# main.net
KiCad netlist of a schematic drawn in Altium Designer
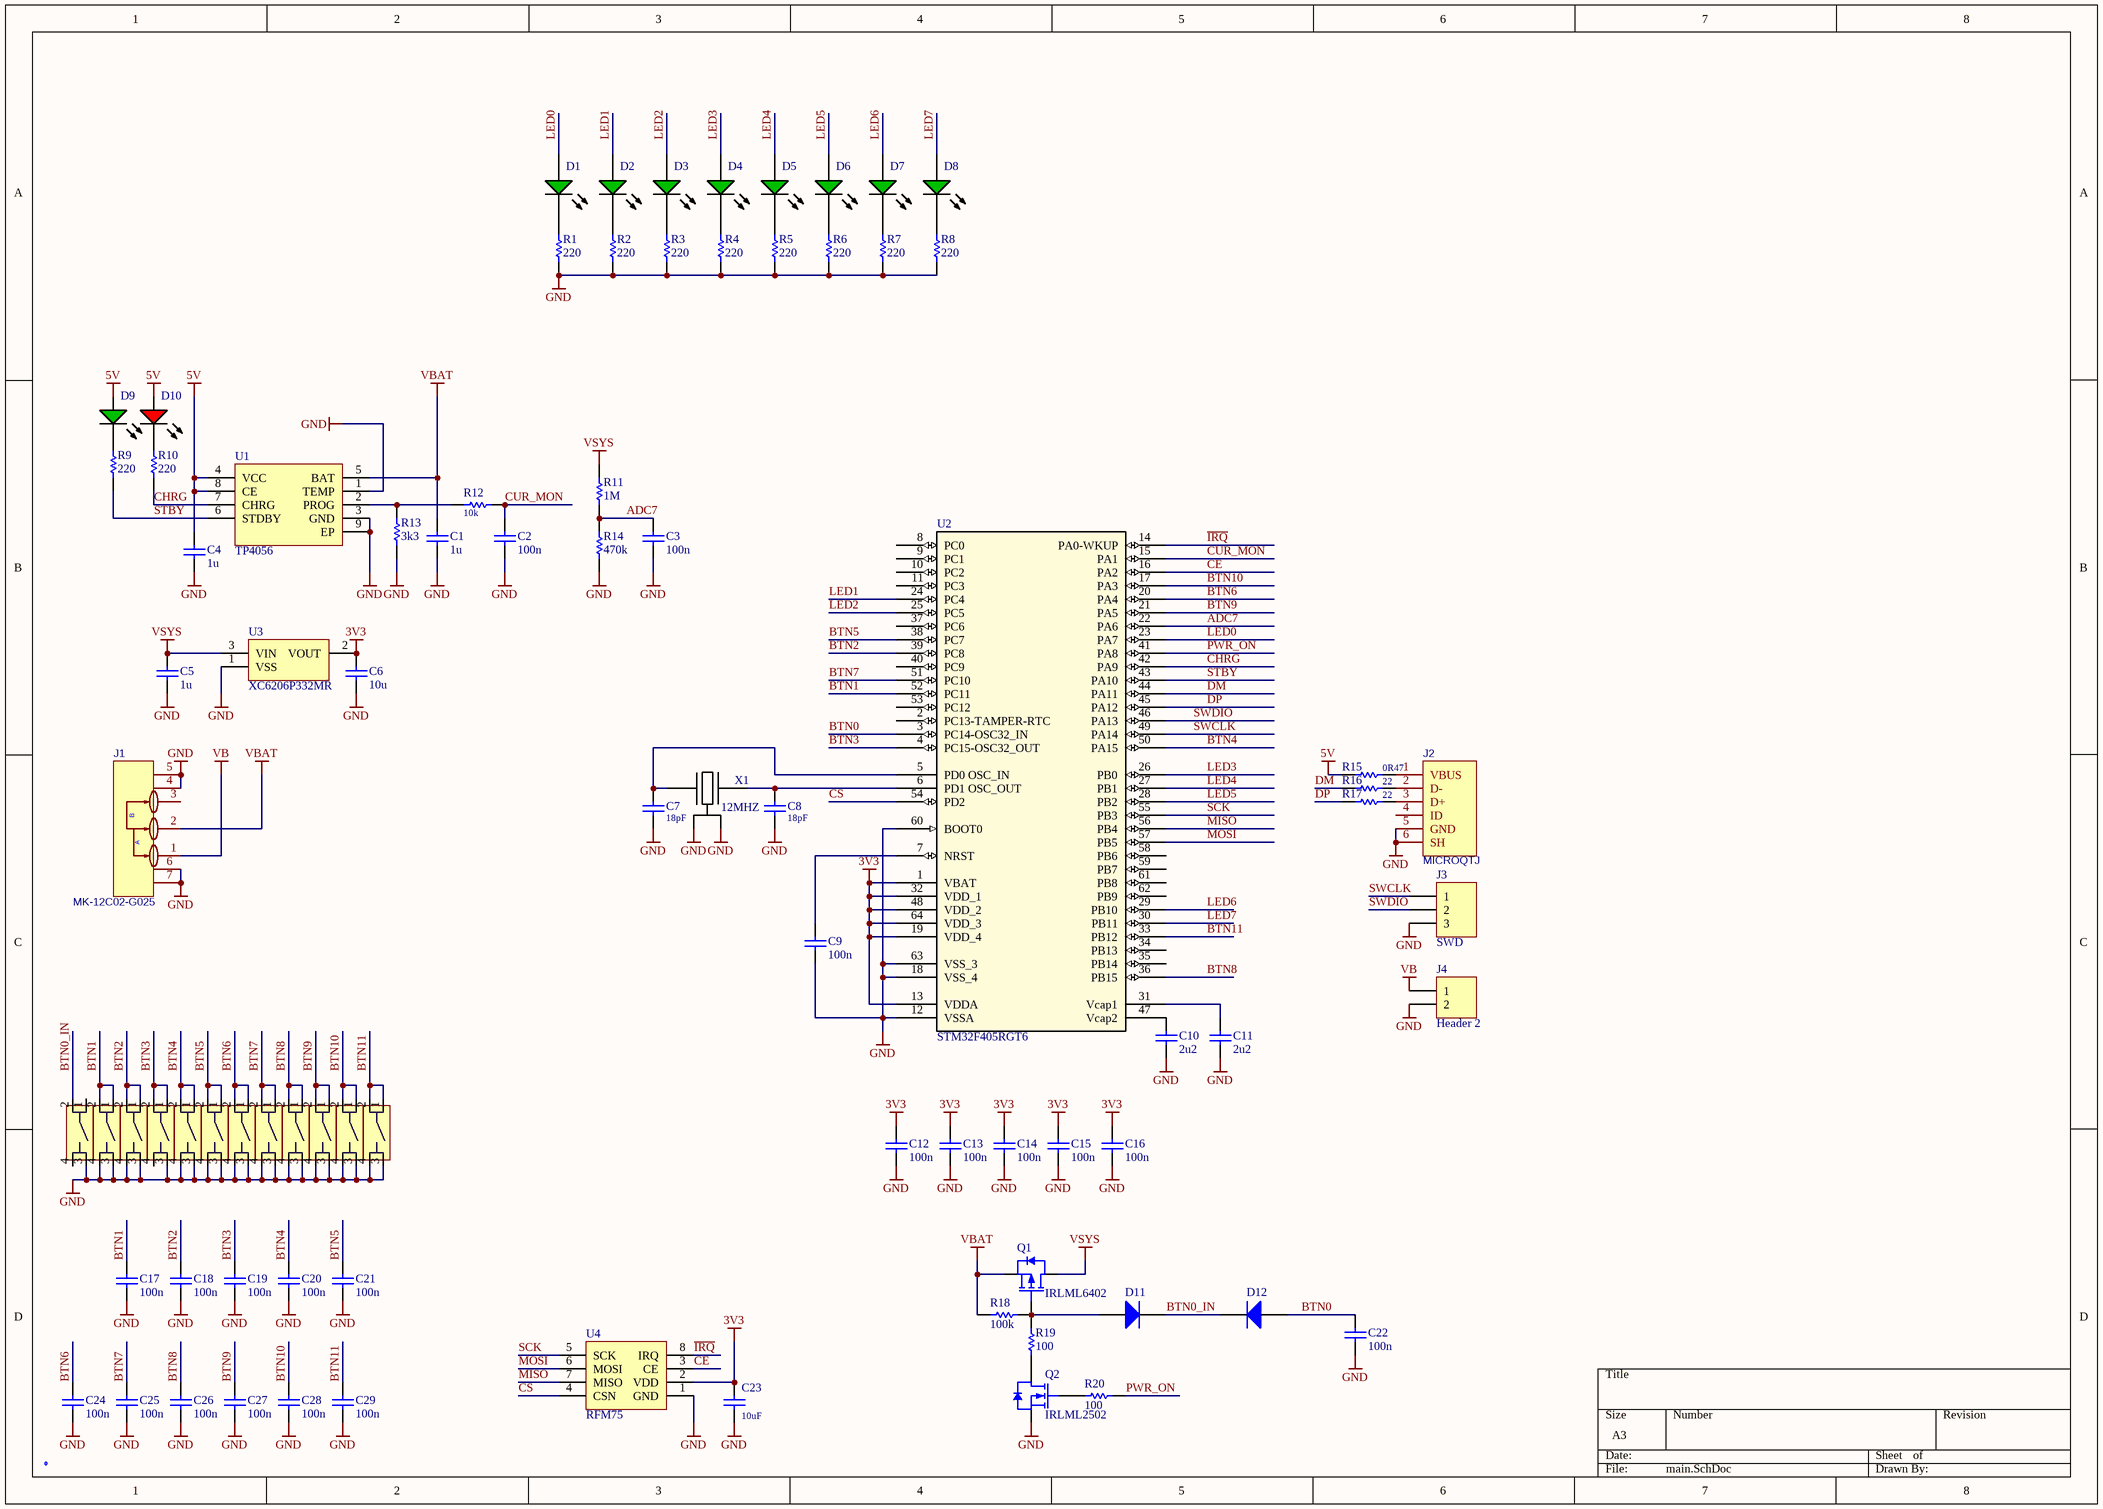
[diagram p0: main.SchDoc]

(export (version "E")
  (design (tool "Eeschema 10.0.6"))
  (components
    (comp (ref "C1") (value "1u") (footprint "C1206") (libsource (lib "Miscellaneous Devices") (part "Cap")))
    (comp (ref "C2")
      (value "100n")
      (footprint "C0603")
      (libsource (lib "Miscellaneous Devices") (part "Cap"))
    )
    (comp (ref "C3")
      (value "100n")
      (footprint "C0603")
      (libsource (lib "Miscellaneous Devices") (part "Cap"))
    )
    (comp (ref "C4") (value "1u") (footprint "C1206") (libsource (lib "Miscellaneous Devices") (part "Cap")))
    (comp (ref "C5") (value "1u") (footprint "C1206") (libsource (lib "Miscellaneous Devices") (part "Cap")))
    (comp (ref "C6") (value "10u") (footprint "C1206") (libsource (lib "Miscellaneous Devices") (part "Cap")))
    (comp (ref "C7")
      (value "18pF")
      (footprint "C0402")
      (description "18pF 0402")
      (libsource (lib "Miscellaneous Devices") (part "CAP"))
    )
    (comp (ref "C8")
      (value "18pF")
      (footprint "C0402")
      (description "18pF 0402")
      (libsource (lib "Miscellaneous Devices") (part "CAP"))
    )
    (comp (ref "C9")
      (value "100n")
      (footprint "C0402")
      (libsource (lib "Miscellaneous Devices") (part "Cap"))
    )
    (comp (ref "C10")
      (value "2u2")
      (footprint "C0603")
      (libsource (lib "Miscellaneous Devices") (part "Cap"))
    )
    (comp (ref "C11")
      (value "2u2")
      (footprint "C0603")
      (libsource (lib "Miscellaneous Devices") (part "Cap"))
    )
    (comp (ref "C12")
      (value "100n")
      (footprint "C0402")
      (libsource (lib "Miscellaneous Devices") (part "Cap"))
    )
    (comp (ref "C13")
      (value "100n")
      (footprint "C0402")
      (libsource (lib "Miscellaneous Devices") (part "Cap"))
    )
    (comp (ref "C14")
      (value "100n")
      (footprint "C0402")
      (libsource (lib "Miscellaneous Devices") (part "Cap"))
    )
    (comp (ref "C15")
      (value "100n")
      (footprint "C0402")
      (libsource (lib "Miscellaneous Devices") (part "Cap"))
    )
    (comp (ref "C16")
      (value "100n")
      (footprint "C0402")
      (libsource (lib "Miscellaneous Devices") (part "Cap"))
    )
    (comp (ref "C17")
      (value "100n")
      (footprint "C0402")
      (libsource (lib "Miscellaneous Devices") (part "Cap"))
    )
    (comp (ref "C18")
      (value "100n")
      (footprint "C0402")
      (libsource (lib "Miscellaneous Devices") (part "Cap"))
    )
    (comp (ref "C19")
      (value "100n")
      (footprint "C0402")
      (libsource (lib "Miscellaneous Devices") (part "Cap"))
    )
    (comp (ref "C20")
      (value "100n")
      (footprint "C0402")
      (libsource (lib "Miscellaneous Devices") (part "Cap"))
    )
    (comp (ref "C21")
      (value "100n")
      (footprint "C0402")
      (libsource (lib "Miscellaneous Devices") (part "Cap"))
    )
    (comp (ref "C22")
      (value "100n")
      (footprint "C0402")
      (libsource (lib "Miscellaneous Devices") (part "Cap"))
    )
    (comp (ref "C23")
      (value "10uF")
      (footprint "C0805")
      (libsource (lib "Miscellaneous Devices") (part "CAP"))
    )
    (comp (ref "C24")
      (value "100n")
      (footprint "C0402")
      (libsource (lib "Miscellaneous Devices") (part "Cap"))
    )
    (comp (ref "C25")
      (value "100n")
      (footprint "C0402")
      (libsource (lib "Miscellaneous Devices") (part "Cap"))
    )
    (comp (ref "C26")
      (value "100n")
      (footprint "C0402")
      (libsource (lib "Miscellaneous Devices") (part "Cap"))
    )
    (comp (ref "C27")
      (value "100n")
      (footprint "C0402")
      (libsource (lib "Miscellaneous Devices") (part "Cap"))
    )
    (comp (ref "C28")
      (value "100n")
      (footprint "C0402")
      (libsource (lib "Miscellaneous Devices") (part "Cap"))
    )
    (comp (ref "C29")
      (value "100n")
      (footprint "C0402")
      (libsource (lib "Miscellaneous Devices") (part "Cap"))
    )
    (comp (ref "D1")
      (value "GRN")
      (footprint "LED-0603-GRN")
      (description "LED 0603 GRN")
      (libsource (lib "Miscellaneous Devices") (part "LED-0603-GREEN"))
    )
    (comp (ref "D2")
      (value "GRN")
      (footprint "LED-0603-GRN")
      (description "LED 0603 GRN")
      (libsource (lib "Miscellaneous Devices") (part "LED-0603-GREEN"))
    )
    (comp (ref "D3")
      (value "GRN")
      (footprint "LED-0603-GRN")
      (description "LED 0603 GRN")
      (libsource (lib "Miscellaneous Devices") (part "LED-0603-GREEN"))
    )
    (comp (ref "D4")
      (value "GRN")
      (footprint "LED-0603-GRN")
      (description "LED 0603 GRN")
      (libsource (lib "Miscellaneous Devices") (part "LED-0603-GREEN"))
    )
    (comp (ref "D5")
      (value "GRN")
      (footprint "LED-0603-GRN")
      (description "LED 0603 GRN")
      (libsource (lib "Miscellaneous Devices") (part "LED-0603-GREEN"))
    )
    (comp (ref "D6")
      (value "GRN")
      (footprint "LED-0603-GRN")
      (description "LED 0603 GRN")
      (libsource (lib "Miscellaneous Devices") (part "LED-0603-GREEN"))
    )
    (comp (ref "D7")
      (value "GRN")
      (footprint "LED-0603-GRN")
      (description "LED 0603 GRN")
      (libsource (lib "Miscellaneous Devices") (part "LED-0603-GREEN"))
    )
    (comp (ref "D8")
      (value "GRN")
      (footprint "LED-0603-GRN")
      (description "LED 0603 GRN")
      (libsource (lib "Miscellaneous Devices") (part "LED-0603-GREEN"))
    )
    (comp (ref "D9")
      (value "GRN")
      (footprint "LED-0603-GRN")
      (description "LED 0603 GRN")
      (libsource (lib "") (part "LED-0603-GREEN_1"))
    )
    (comp (ref "D10")
      (value "RED")
      (footprint "LED-0603-RED")
      (description "LED 0603 RED")
      (libsource (lib "Miscellaneous Devices") (part "LED-0603-RED"))
    )
    (comp (ref "D11")
      (value "~")
      (footprint "SOD-323")
      (libsource (lib "Miscellaneous Devices") (part "US1M-13-F"))
    )
    (comp (ref "D12")
      (value "~")
      (footprint "SOD-323")
      (libsource (lib "Miscellaneous Devices") (part "US1M-13-F"))
    )
    (comp (ref "J1")
      (value "MK-12C02-G025")
      (footprint "SW-SMD_MK-12C02-G025")
      (libsource (lib "Schlib1") (part "MK-12C02-G025"))
    )
    (comp (ref "J2")
      (value "MICROQTJ")
      (footprint "CONN-USB-MICRO_#1")
      (libsource (lib "Schlib2") (part "MICROQTJ"))
    )
    (comp (ref "J3")
      (value "SWD")
      (footprint "HDR-1X3_2.54")
      (libsource (lib "Miscellaneous Devices") (part "Header 3"))
    )
    (comp (ref "J4")
      (value "Header 2")
      (footprint "HDR-1X2_2.54")
      (libsource (lib "Schlib1") (part "Header 2"))
    )
    (comp (ref "LOGO1") (value "LOGO") (footprint "LOGO") (libsource (lib "Schlib1") (part "LOGO")))
    (comp (ref "Q1") (value "IRLML6402") (footprint "SOT-23") (libsource (lib "") (part "2N7002_1")))
    (comp (ref "Q2")
      (value "IRLML2502")
      (footprint "SOT-23")
      (description "AOD4184")
      (libsource (lib "Miscellaneous Devices") (part "2N7002"))
    )
    (comp (ref "R1")
      (value "220")
      (footprint "R0603")
      (libsource (lib "Miscellaneous Devices") (part "Res1"))
    )
    (comp (ref "R2")
      (value "220")
      (footprint "R0603")
      (libsource (lib "Miscellaneous Devices") (part "Res1"))
    )
    (comp (ref "R3")
      (value "220")
      (footprint "R0603")
      (libsource (lib "Miscellaneous Devices") (part "Res1"))
    )
    (comp (ref "R4")
      (value "220")
      (footprint "R0603")
      (libsource (lib "Miscellaneous Devices") (part "Res1"))
    )
    (comp (ref "R5")
      (value "220")
      (footprint "R0603")
      (libsource (lib "Miscellaneous Devices") (part "Res1"))
    )
    (comp (ref "R6")
      (value "220")
      (footprint "R0603")
      (libsource (lib "Miscellaneous Devices") (part "Res1"))
    )
    (comp (ref "R7")
      (value "220")
      (footprint "R0603")
      (libsource (lib "Miscellaneous Devices") (part "Res1"))
    )
    (comp (ref "R8")
      (value "220")
      (footprint "R0603")
      (libsource (lib "Miscellaneous Devices") (part "Res1"))
    )
    (comp (ref "R9")
      (value "220")
      (footprint "R0603")
      (libsource (lib "Miscellaneous Devices") (part "Res1"))
    )
    (comp (ref "R10")
      (value "220")
      (footprint "R0603")
      (libsource (lib "Miscellaneous Devices") (part "Res1"))
    )
    (comp (ref "R11")
      (value "1M")
      (footprint "R0603")
      (libsource (lib "Miscellaneous Devices") (part "Res1"))
    )
    (comp (ref "R12")
      (value "10k")
      (footprint "R0603")
      (libsource (lib "Miscellaneous Devices") (part "RES"))
    )
    (comp (ref "R13")
      (value "3k3")
      (footprint "R0603")
      (libsource (lib "Miscellaneous Devices") (part "Res1"))
    )
    (comp (ref "R14")
      (value "470k")
      (footprint "R0603")
      (libsource (lib "Miscellaneous Devices") (part "Res1"))
    )
    (comp (ref "R15")
      (value "0R47")
      (footprint "R0603")
      (libsource (lib "Miscellaneous Devices") (part "RES"))
    )
    (comp (ref "R16") (value "22") (footprint "R0603") (libsource (lib "Miscellaneous Devices") (part "RES")))
    (comp (ref "R17") (value "22") (footprint "R0603") (libsource (lib "Miscellaneous Devices") (part "RES")))
    (comp (ref "R18")
      (value "100k")
      (footprint "R0603")
      (libsource (lib "Miscellaneous Devices") (part "Res1"))
    )
    (comp (ref "R19")
      (value "100")
      (footprint "R0603")
      (libsource (lib "Miscellaneous Devices") (part "Res1"))
    )
    (comp (ref "R20")
      (value "100")
      (footprint "R0603")
      (libsource (lib "Miscellaneous Devices") (part "Res1"))
    )
    (comp (ref "SW1")
      (value "PTS810SJS250")
      (footprint "BTN_PTS810")
      (libsource (lib "Miscellaneous Devices") (part "Component_1"))
    )
    (comp (ref "SW2")
      (value "PTS810SJS250")
      (footprint "BTN_PTS810")
      (libsource (lib "Miscellaneous Devices") (part "Component_1"))
    )
    (comp (ref "SW3")
      (value "PTS810SJS250")
      (footprint "BTN_PTS810")
      (libsource (lib "Miscellaneous Devices") (part "Component_1"))
    )
    (comp (ref "SW4")
      (value "PTS810SJS250")
      (footprint "BTN_PTS810")
      (libsource (lib "Miscellaneous Devices") (part "Component_1"))
    )
    (comp (ref "SW5")
      (value "PTS810SJS250")
      (footprint "BTN_PTS810")
      (libsource (lib "Miscellaneous Devices") (part "Component_1"))
    )
    (comp (ref "SW6")
      (value "PTS810SJS250")
      (footprint "BTN_PTS810")
      (libsource (lib "Miscellaneous Devices") (part "Component_1"))
    )
    (comp (ref "SW7")
      (value "PTS810SJS250")
      (footprint "BTN_PTS810")
      (libsource (lib "Miscellaneous Devices") (part "Component_1"))
    )
    (comp (ref "SW8")
      (value "PTS810SJS250")
      (footprint "BTN_PTS810")
      (libsource (lib "Miscellaneous Devices") (part "Component_1"))
    )
    (comp (ref "SW9")
      (value "PTS810SJS250")
      (footprint "BTN_PTS810")
      (libsource (lib "Miscellaneous Devices") (part "Component_1"))
    )
    (comp (ref "SW10")
      (value "PTS810SJS250")
      (footprint "BTN_PTS810")
      (libsource (lib "Miscellaneous Devices") (part "Component_1"))
    )
    (comp (ref "SW11")
      (value "PTS810SJS250")
      (footprint "BTN_PTS810")
      (libsource (lib "Miscellaneous Devices") (part "Component_1"))
    )
    (comp (ref "SW12")
      (value "PTS810SJS250")
      (footprint "BTN_PTS810")
      (libsource (lib "Miscellaneous Devices") (part "Component_1"))
    )
    (comp (ref "U1") (value "TP4056") (footprint "PowerSOIC-8") (libsource (lib "Schlib1") (part "TP4056")))
    (comp (ref "U2")
      (value "STM32F405RGT6")
      (footprint "LQFP-64")
      (description "MCU STM32F405RGT6")
      (libsource (lib "RozumLibrary") (part "STM32F405RGT6"))
    )
    (comp (ref "U3")
      (value "XC6206P332MR")
      (footprint "SOT-23")
      (libsource (lib "Schlib1") (part "Component_4_1"))
    )
    (comp (ref "U4") (value "RFM75") (footprint "RFM75") (libsource (lib "Schlib1") (part "RFM75")))
    (comp (ref "X1")
      (value "12MHZ")
      (footprint "CRYSTAL_3.2x2.5mm")
      (description "X322512MOB4SI")
      (libsource (lib "Miscellaneous Devices") (part "CRYSTAL 12MHZ 3.20mm x 2.50mm"))
    )
  )
  (nets
    (net (code "1") (name "/ADC7") (class "Default")
      (node (ref "C3") (pin "2") (pinfunction "2_2") (pintype "passive"))
      (node (ref "R11") (pin "1") (pinfunction "1_1") (pintype "passive"))
      (node (ref "R14") (pin "2") (pinfunction "2_2") (pintype "passive"))
      (node (ref "U2") (pin "22") (pinfunction "PA6_22") (pintype "bidirectional"))
    )
    (net (code "2") (name "/BTN0") (class "Default")
      (node (ref "C22") (pin "2") (pinfunction "2_2") (pintype "passive"))
      (node (ref "D12") (pin "1") (pinfunction "A_1") (pintype "passive"))
      (node (ref "U2") (pin "3") (pinfunction "PC14-OSC32_IN_3") (pintype "bidirectional"))
    )
    (net (code "3") (name "/BTN0_IN") (class "Default")
      (node (ref "D11") (pin "2") (pinfunction "K_2") (pintype "passive"))
      (node (ref "D12") (pin "2") (pinfunction "K_2") (pintype "passive"))
      (node (ref "SW1") (pin "2") (pinfunction "2_2") (pintype "passive"))
    )
    (net (code "4") (name "/BTN1") (class "Default")
      (node (ref "C17") (pin "2") (pinfunction "2_2") (pintype "passive"))
      (node (ref "SW2") (pin "1") (pinfunction "1_1") (pintype "passive"))
      (node (ref "SW2") (pin "2") (pinfunction "2_2") (pintype "passive"))
      (node (ref "U2") (pin "52") (pinfunction "PC11_52") (pintype "bidirectional"))
    )
    (net (code "5") (name "/BTN2") (class "Default")
      (node (ref "C18") (pin "2") (pinfunction "2_2") (pintype "passive"))
      (node (ref "SW3") (pin "1") (pinfunction "1_1") (pintype "passive"))
      (node (ref "SW3") (pin "2") (pinfunction "2_2") (pintype "passive"))
      (node (ref "U2") (pin "39") (pinfunction "PC8_39") (pintype "bidirectional"))
    )
    (net (code "6") (name "/BTN3") (class "Default")
      (node (ref "C19") (pin "2") (pinfunction "2_2") (pintype "passive"))
      (node (ref "SW4") (pin "1") (pinfunction "1_1") (pintype "passive"))
      (node (ref "SW4") (pin "2") (pinfunction "2_2") (pintype "passive"))
      (node (ref "U2") (pin "4") (pinfunction "PC15-OSC32_OUT_4") (pintype "bidirectional"))
    )
    (net (code "7") (name "/BTN4") (class "Default")
      (node (ref "C20") (pin "2") (pinfunction "2_2") (pintype "passive"))
      (node (ref "SW5") (pin "1") (pinfunction "1_1") (pintype "passive"))
      (node (ref "SW5") (pin "2") (pinfunction "2_2") (pintype "passive"))
      (node (ref "U2") (pin "50") (pinfunction "PA15_50") (pintype "bidirectional"))
    )
    (net (code "8") (name "/BTN5") (class "Default")
      (node (ref "C21") (pin "2") (pinfunction "2_2") (pintype "passive"))
      (node (ref "SW6") (pin "1") (pinfunction "1_1") (pintype "passive"))
      (node (ref "SW6") (pin "2") (pinfunction "2_2") (pintype "passive"))
      (node (ref "U2") (pin "38") (pinfunction "PC7_38") (pintype "bidirectional"))
    )
    (net (code "9") (name "/BTN6") (class "Default")
      (node (ref "C24") (pin "2") (pinfunction "2_2") (pintype "passive"))
      (node (ref "SW7") (pin "1") (pinfunction "1_1") (pintype "passive"))
      (node (ref "SW7") (pin "2") (pinfunction "2_2") (pintype "passive"))
      (node (ref "U2") (pin "20") (pinfunction "PA4_20") (pintype "bidirectional"))
    )
    (net (code "10") (name "/BTN7") (class "Default")
      (node (ref "C25") (pin "2") (pinfunction "2_2") (pintype "passive"))
      (node (ref "SW8") (pin "1") (pinfunction "1_1") (pintype "passive"))
      (node (ref "SW8") (pin "2") (pinfunction "2_2") (pintype "passive"))
      (node (ref "U2") (pin "51") (pinfunction "PC10_51") (pintype "bidirectional"))
    )
    (net (code "11") (name "/BTN8") (class "Default")
      (node (ref "C26") (pin "2") (pinfunction "2_2") (pintype "passive"))
      (node (ref "SW9") (pin "1") (pinfunction "1_1") (pintype "passive"))
      (node (ref "SW9") (pin "2") (pinfunction "2_2") (pintype "passive"))
      (node (ref "U2") (pin "36") (pinfunction "PB15_36") (pintype "bidirectional"))
    )
    (net (code "12") (name "/BTN9") (class "Default")
      (node (ref "C27") (pin "2") (pinfunction "2_2") (pintype "passive"))
      (node (ref "SW10") (pin "1") (pinfunction "1_1") (pintype "passive"))
      (node (ref "SW10") (pin "2") (pinfunction "2_2") (pintype "passive"))
      (node (ref "U2") (pin "21") (pinfunction "PA5_21") (pintype "bidirectional"))
    )
    (net (code "13") (name "/BTN10") (class "Default")
      (node (ref "C28") (pin "2") (pinfunction "2_2") (pintype "passive"))
      (node (ref "SW11") (pin "1") (pinfunction "1_1") (pintype "passive"))
      (node (ref "SW11") (pin "2") (pinfunction "2_2") (pintype "passive"))
      (node (ref "U2") (pin "17") (pinfunction "PA3_17") (pintype "bidirectional"))
    )
    (net (code "14") (name "/BTN11") (class "Default")
      (node (ref "C29") (pin "2") (pinfunction "2_2") (pintype "passive"))
      (node (ref "SW12") (pin "1") (pinfunction "1_1") (pintype "passive"))
      (node (ref "SW12") (pin "2") (pinfunction "2_2") (pintype "passive"))
      (node (ref "U2") (pin "33") (pinfunction "PB12_33") (pintype "bidirectional"))
    )
    (net (code "15") (name "/CE") (class "Default")
      (node (ref "U2") (pin "16") (pinfunction "PA2_16") (pintype "bidirectional"))
      (node (ref "U4") (pin "3") (pinfunction "CE_3") (pintype "passive"))
    )
    (net (code "16") (name "/CHRG") (class "Default")
      (node (ref "R10") (pin "1") (pinfunction "1_1") (pintype "passive"))
      (node (ref "U1") (pin "7") (pinfunction "CHRG_7") (pintype "passive"))
      (node (ref "U2") (pin "42") (pinfunction "PA9_42") (pintype "bidirectional"))
    )
    (net (code "17") (name "/CUR_MON") (class "Default")
      (node (ref "C2") (pin "2") (pinfunction "2_2") (pintype "passive"))
      (node (ref "R12") (pin "1") (pinfunction "1_1") (pintype "passive"))
      (node (ref "U2") (pin "15") (pinfunction "PA1_15") (pintype "bidirectional"))
    )
    (net (code "18") (name "/DM") (class "Default")
      (node (ref "R16") (pin "2") (pinfunction "2_2") (pintype "passive"))
      (node (ref "U2") (pin "44") (pinfunction "PA11_44") (pintype "bidirectional"))
    )
    (net (code "19") (name "/DP") (class "Default")
      (node (ref "R17") (pin "2") (pinfunction "2_2") (pintype "passive"))
      (node (ref "U2") (pin "45") (pinfunction "PA12_45") (pintype "bidirectional"))
    )
    (net (code "20") (name "/LED0") (class "Default")
      (node (ref "D1") (pin "1") (pinfunction "A_1") (pintype "passive"))
      (node (ref "U2") (pin "23") (pinfunction "PA7_23") (pintype "bidirectional"))
    )
    (net (code "21") (name "/LED1") (class "Default")
      (node (ref "D2") (pin "1") (pinfunction "A_1") (pintype "passive"))
      (node (ref "U2") (pin "24") (pinfunction "PC4_24") (pintype "bidirectional"))
    )
    (net (code "22") (name "/LED2") (class "Default")
      (node (ref "D3") (pin "1") (pinfunction "A_1") (pintype "passive"))
      (node (ref "U2") (pin "25") (pinfunction "PC5_25") (pintype "bidirectional"))
    )
    (net (code "23") (name "/LED3") (class "Default")
      (node (ref "D4") (pin "1") (pinfunction "A_1") (pintype "passive"))
      (node (ref "U2") (pin "26") (pinfunction "PB0_26") (pintype "bidirectional"))
    )
    (net (code "24") (name "/LED4") (class "Default")
      (node (ref "D5") (pin "1") (pinfunction "A_1") (pintype "passive"))
      (node (ref "U2") (pin "27") (pinfunction "PB1_27") (pintype "bidirectional"))
    )
    (net (code "25") (name "/LED5") (class "Default")
      (node (ref "D6") (pin "1") (pinfunction "A_1") (pintype "passive"))
      (node (ref "U2") (pin "28") (pinfunction "PB2_28") (pintype "bidirectional"))
    )
    (net (code "26") (name "/LED6") (class "Default")
      (node (ref "D7") (pin "1") (pinfunction "A_1") (pintype "passive"))
      (node (ref "U2") (pin "29") (pinfunction "PB10_29") (pintype "bidirectional"))
    )
    (net (code "27") (name "/LED7") (class "Default")
      (node (ref "D8") (pin "1") (pinfunction "A_1") (pintype "passive"))
      (node (ref "U2") (pin "30") (pinfunction "PB11_30") (pintype "bidirectional"))
    )
    (net (code "28") (name "/MISO") (class "Default")
      (node (ref "U2") (pin "56") (pinfunction "PB4_56") (pintype "bidirectional"))
      (node (ref "U4") (pin "7") (pinfunction "MISO_7") (pintype "passive"))
    )
    (net (code "29") (name "/MOSI") (class "Default")
      (node (ref "U2") (pin "57") (pinfunction "PB5_57") (pintype "bidirectional"))
      (node (ref "U4") (pin "6") (pinfunction "MOSI_6") (pintype "passive"))
    )
    (net (code "30") (name "/PWR_ON") (class "Default")
      (node (ref "R20") (pin "1") (pinfunction "1_1") (pintype "passive"))
      (node (ref "U2") (pin "41") (pinfunction "PA8_41") (pintype "bidirectional"))
    )
    (net (code "31") (name "/SCK") (class "Default")
      (node (ref "U2") (pin "55") (pinfunction "PB3_55") (pintype "bidirectional"))
      (node (ref "U4") (pin "5") (pinfunction "SCK_5") (pintype "passive"))
    )
    (net (code "32") (name "/STBY") (class "Default")
      (node (ref "R9") (pin "1") (pinfunction "1_1") (pintype "passive"))
      (node (ref "U1") (pin "6") (pinfunction "STDBY_6") (pintype "passive"))
      (node (ref "U2") (pin "43") (pinfunction "PA10_43") (pintype "bidirectional"))
    )
    (net (code "33") (name "/SWCLK") (class "Default")
      (node (ref "J3") (pin "1") (pinfunction "1_1") (pintype "passive"))
      (node (ref "U2") (pin "49") (pinfunction "PA14_49") (pintype "bidirectional"))
    )
    (net (code "34") (name "/SWDIO") (class "Default")
      (node (ref "J3") (pin "2") (pinfunction "2_2") (pintype "passive"))
      (node (ref "U2") (pin "46") (pinfunction "PA13_46") (pintype "bidirectional"))
    )
    (net (code "35") (name "/~{CS}") (class "Default")
      (node (ref "U2") (pin "54") (pinfunction "PD2_54") (pintype "bidirectional"))
      (node (ref "U4") (pin "4") (pinfunction "CSN_4") (pintype "passive"))
    )
    (net (code "36") (name "/~{IRQ}") (class "Default")
      (node (ref "U2") (pin "14") (pinfunction "PA0-WKUP_14") (pintype "bidirectional"))
      (node (ref "U4") (pin "8") (pinfunction "IRQ_8") (pintype "passive"))
    )
    (net (code "37") (name "3V3") (class "Default")
      (node (ref "C12") (pin "2") (pinfunction "2_2") (pintype "passive"))
      (node (ref "C13") (pin "2") (pinfunction "2_2") (pintype "passive"))
      (node (ref "C14") (pin "2") (pinfunction "2_2") (pintype "passive"))
      (node (ref "C15") (pin "2") (pinfunction "2_2") (pintype "passive"))
      (node (ref "C16") (pin "2") (pinfunction "2_2") (pintype "passive"))
      (node (ref "C23") (pin "2") (pinfunction "2_2") (pintype "passive"))
      (node (ref "C6") (pin "2") (pinfunction "2_2") (pintype "passive"))
      (node (ref "U2") (pin "1") (pinfunction "VBAT_1") (pintype "power_in"))
      (node (ref "U2") (pin "13") (pinfunction "VDDA_13") (pintype "power_in"))
      (node (ref "U2") (pin "19") (pinfunction "VDD_4_19") (pintype "power_in"))
      (node (ref "U2") (pin "32") (pinfunction "VDD_1_32") (pintype "power_in"))
      (node (ref "U2") (pin "48") (pinfunction "VDD_2_48") (pintype "power_in"))
      (node (ref "U2") (pin "64") (pinfunction "VDD_3_64") (pintype "power_in"))
      (node (ref "U3") (pin "2") (pinfunction "VOUT_2") (pintype "passive"))
      (node (ref "U4") (pin "2") (pinfunction "VDD_2") (pintype "passive"))
    )
    (net (code "38") (name "5V") (class "Default")
      (node (ref "C4") (pin "2") (pinfunction "2_2") (pintype "passive"))
      (node (ref "D10") (pin "1") (pinfunction "A_1") (pintype "passive"))
      (node (ref "D9") (pin "1") (pinfunction "A_1") (pintype "passive"))
      (node (ref "R15") (pin "2") (pinfunction "2_2") (pintype "passive"))
      (node (ref "U1") (pin "4") (pinfunction "VCC_4") (pintype "passive"))
      (node (ref "U1") (pin "8") (pinfunction "CE_8") (pintype "passive"))
    )
    (net (code "39") (name "GND") (class "Default")
      (node (ref "C1") (pin "1") (pinfunction "1_1") (pintype "passive"))
      (node (ref "C10") (pin "1") (pinfunction "1_1") (pintype "passive"))
      (node (ref "C11") (pin "1") (pinfunction "1_1") (pintype "passive"))
      (node (ref "C12") (pin "1") (pinfunction "1_1") (pintype "passive"))
      (node (ref "C13") (pin "1") (pinfunction "1_1") (pintype "passive"))
      (node (ref "C14") (pin "1") (pinfunction "1_1") (pintype "passive"))
      (node (ref "C15") (pin "1") (pinfunction "1_1") (pintype "passive"))
      (node (ref "C16") (pin "1") (pinfunction "1_1") (pintype "passive"))
      (node (ref "C17") (pin "1") (pinfunction "1_1") (pintype "passive"))
      (node (ref "C18") (pin "1") (pinfunction "1_1") (pintype "passive"))
      (node (ref "C19") (pin "1") (pinfunction "1_1") (pintype "passive"))
      (node (ref "C2") (pin "1") (pinfunction "1_1") (pintype "passive"))
      (node (ref "C20") (pin "1") (pinfunction "1_1") (pintype "passive"))
      (node (ref "C21") (pin "1") (pinfunction "1_1") (pintype "passive"))
      (node (ref "C22") (pin "1") (pinfunction "1_1") (pintype "passive"))
      (node (ref "C23") (pin "1") (pinfunction "1_1") (pintype "passive"))
      (node (ref "C24") (pin "1") (pinfunction "1_1") (pintype "passive"))
      (node (ref "C25") (pin "1") (pinfunction "1_1") (pintype "passive"))
      (node (ref "C26") (pin "1") (pinfunction "1_1") (pintype "passive"))
      (node (ref "C27") (pin "1") (pinfunction "1_1") (pintype "passive"))
      (node (ref "C28") (pin "1") (pinfunction "1_1") (pintype "passive"))
      (node (ref "C29") (pin "1") (pinfunction "1_1") (pintype "passive"))
      (node (ref "C3") (pin "1") (pinfunction "1_1") (pintype "passive"))
      (node (ref "C4") (pin "1") (pinfunction "1_1") (pintype "passive"))
      (node (ref "C5") (pin "1") (pinfunction "1_1") (pintype "passive"))
      (node (ref "C6") (pin "1") (pinfunction "1_1") (pintype "passive"))
      (node (ref "C7") (pin "1") (pinfunction "1_1") (pintype "passive"))
      (node (ref "C8") (pin "1") (pinfunction "1_1") (pintype "passive"))
      (node (ref "C9") (pin "1") (pinfunction "1_1") (pintype "passive"))
      (node (ref "J1") (pin "4") (pinfunction "4_4") (pintype "passive"))
      (node (ref "J1") (pin "5") (pinfunction "5_5") (pintype "passive"))
      (node (ref "J1") (pin "6") (pinfunction "6_6") (pintype "passive"))
      (node (ref "J1") (pin "7") (pinfunction "7_7") (pintype "passive"))
      (node (ref "J2") (pin "5") (pinfunction "GND_5") (pintype "passive"))
      (node (ref "J2") (pin "6") (pinfunction "SH_6") (pintype "passive"))
      (node (ref "J3") (pin "3") (pinfunction "3_3") (pintype "passive"))
      (node (ref "J4") (pin "2") (pinfunction "2_2") (pintype "passive"))
      (node (ref "Q2") (pin "2") (pinfunction "SOURCE_2") (pintype "passive"))
      (node (ref "R1") (pin "1") (pinfunction "1_1") (pintype "passive"))
      (node (ref "R13") (pin "1") (pinfunction "1_1") (pintype "passive"))
      (node (ref "R14") (pin "1") (pinfunction "1_1") (pintype "passive"))
      (node (ref "R2") (pin "1") (pinfunction "1_1") (pintype "passive"))
      (node (ref "R3") (pin "1") (pinfunction "1_1") (pintype "passive"))
      (node (ref "R4") (pin "1") (pinfunction "1_1") (pintype "passive"))
      (node (ref "R5") (pin "1") (pinfunction "1_1") (pintype "passive"))
      (node (ref "R6") (pin "1") (pinfunction "1_1") (pintype "passive"))
      (node (ref "R7") (pin "1") (pinfunction "1_1") (pintype "passive"))
      (node (ref "R8") (pin "1") (pinfunction "1_1") (pintype "passive"))
      (node (ref "SW1") (pin "3") (pinfunction "3_3") (pintype "passive"))
      (node (ref "SW10") (pin "3") (pinfunction "3_3") (pintype "passive"))
      (node (ref "SW10") (pin "4") (pinfunction "4_4") (pintype "passive"))
      (node (ref "SW11") (pin "3") (pinfunction "3_3") (pintype "passive"))
      (node (ref "SW11") (pin "4") (pinfunction "4_4") (pintype "passive"))
      (node (ref "SW12") (pin "3") (pinfunction "3_3") (pintype "passive"))
      (node (ref "SW12") (pin "4") (pinfunction "4_4") (pintype "passive"))
      (node (ref "SW2") (pin "3") (pinfunction "3_3") (pintype "passive"))
      (node (ref "SW2") (pin "4") (pinfunction "4_4") (pintype "passive"))
      (node (ref "SW3") (pin "3") (pinfunction "3_3") (pintype "passive"))
      (node (ref "SW3") (pin "4") (pinfunction "4_4") (pintype "passive"))
      (node (ref "SW4") (pin "3") (pinfunction "3_3") (pintype "passive"))
      (node (ref "SW5") (pin "3") (pinfunction "3_3") (pintype "passive"))
      (node (ref "SW5") (pin "4") (pinfunction "4_4") (pintype "passive"))
      (node (ref "SW6") (pin "3") (pinfunction "3_3") (pintype "passive"))
      (node (ref "SW6") (pin "4") (pinfunction "4_4") (pintype "passive"))
      (node (ref "SW7") (pin "3") (pinfunction "3_3") (pintype "passive"))
      (node (ref "SW7") (pin "4") (pinfunction "4_4") (pintype "passive"))
      (node (ref "SW8") (pin "3") (pinfunction "3_3") (pintype "passive"))
      (node (ref "SW8") (pin "4") (pinfunction "4_4") (pintype "passive"))
      (node (ref "SW9") (pin "3") (pinfunction "3_3") (pintype "passive"))
      (node (ref "SW9") (pin "4") (pinfunction "4_4") (pintype "passive"))
      (node (ref "U1") (pin "1") (pinfunction "TEMP_1") (pintype "passive"))
      (node (ref "U1") (pin "3") (pinfunction "GND_3") (pintype "passive"))
      (node (ref "U1") (pin "9") (pinfunction "EP_9") (pintype "passive"))
      (node (ref "U2") (pin "12") (pinfunction "VSSA_12") (pintype "power_in"))
      (node (ref "U2") (pin "18") (pinfunction "VSS_4_18") (pintype "power_in"))
      (node (ref "U2") (pin "60") (pinfunction "BOOT0_60") (pintype "input"))
      (node (ref "U2") (pin "63") (pinfunction "VSS_3_63") (pintype "power_in"))
      (node (ref "U3") (pin "1") (pinfunction "VSS_1") (pintype "passive"))
      (node (ref "U4") (pin "1") (pinfunction "GND_1") (pintype "passive"))
      (node (ref "X1") (pin "2") (pinfunction "GND_2") (pintype "passive"))
      (node (ref "X1") (pin "4") (pinfunction "GND_4") (pintype "passive"))
    )
    (net (code "40") (name "Net-(D1-K)") (class "Default")
      (node (ref "D1") (pin "2") (pinfunction "K_2") (pintype "passive"))
      (node (ref "R1") (pin "2") (pinfunction "2_2") (pintype "passive"))
    )
    (net (code "41") (name "Net-(D2-K)") (class "Default")
      (node (ref "D2") (pin "2") (pinfunction "K_2") (pintype "passive"))
      (node (ref "R2") (pin "2") (pinfunction "2_2") (pintype "passive"))
    )
    (net (code "42") (name "Net-(D3-K)") (class "Default")
      (node (ref "D3") (pin "2") (pinfunction "K_2") (pintype "passive"))
      (node (ref "R3") (pin "2") (pinfunction "2_2") (pintype "passive"))
    )
    (net (code "43") (name "Net-(D4-K)") (class "Default")
      (node (ref "D4") (pin "2") (pinfunction "K_2") (pintype "passive"))
      (node (ref "R4") (pin "2") (pinfunction "2_2") (pintype "passive"))
    )
    (net (code "44") (name "Net-(D5-K)") (class "Default")
      (node (ref "D5") (pin "2") (pinfunction "K_2") (pintype "passive"))
      (node (ref "R5") (pin "2") (pinfunction "2_2") (pintype "passive"))
    )
    (net (code "45") (name "Net-(D6-K)") (class "Default")
      (node (ref "D6") (pin "2") (pinfunction "K_2") (pintype "passive"))
      (node (ref "R6") (pin "2") (pinfunction "2_2") (pintype "passive"))
    )
    (net (code "46") (name "Net-(D7-K)") (class "Default")
      (node (ref "D7") (pin "2") (pinfunction "K_2") (pintype "passive"))
      (node (ref "R7") (pin "2") (pinfunction "2_2") (pintype "passive"))
    )
    (net (code "47") (name "Net-(D8-K)") (class "Default")
      (node (ref "D8") (pin "2") (pinfunction "K_2") (pintype "passive"))
      (node (ref "R8") (pin "2") (pinfunction "2_2") (pintype "passive"))
    )
    (net (code "48") (name "Net-(D9-K)") (class "Default")
      (node (ref "D9") (pin "2") (pinfunction "K_2") (pintype "passive"))
      (node (ref "R9") (pin "2") (pinfunction "2_2") (pintype "passive"))
    )
    (net (code "49") (name "Net-(D10-K)") (class "Default")
      (node (ref "D10") (pin "2") (pinfunction "K_2") (pintype "passive"))
      (node (ref "R10") (pin "2") (pinfunction "2_2") (pintype "passive"))
    )
    (net (code "50") (name "Net-(D11-A)") (class "Default")
      (node (ref "D11") (pin "1") (pinfunction "A_1") (pintype "passive"))
      (node (ref "Q1") (pin "1") (pinfunction "GATE_1") (pintype "passive"))
      (node (ref "R18") (pin "1") (pinfunction "1_1") (pintype "passive"))
      (node (ref "R19") (pin "2") (pinfunction "2_2") (pintype "passive"))
    )
    (net (code "51") (name "Net-(J2-D+)") (class "Default")
      (node (ref "J2") (pin "3") (pinfunction "D+_3") (pintype "passive"))
      (node (ref "R17") (pin "1") (pinfunction "1_1") (pintype "passive"))
    )
    (net (code "52") (name "Net-(J2-D-)") (class "Default")
      (node (ref "J2") (pin "2") (pinfunction "D-_2") (pintype "passive"))
      (node (ref "R16") (pin "1") (pinfunction "1_1") (pintype "passive"))
    )
    (net (code "53") (name "Net-(J2-VBUS)") (class "Default")
      (node (ref "J2") (pin "1") (pinfunction "VBUS_1") (pintype "passive"))
      (node (ref "R15") (pin "1") (pinfunction "1_1") (pintype "passive"))
    )
    (net (code "54") (name "Net-(Q2-DRAIN)") (class "Default")
      (node (ref "Q2") (pin "3") (pinfunction "DRAIN_3") (pintype "passive"))
      (node (ref "R19") (pin "1") (pinfunction "1_1") (pintype "passive"))
    )
    (net (code "55") (name "Net-(Q2-GATE)") (class "Default")
      (node (ref "Q2") (pin "1") (pinfunction "GATE_1") (pintype "passive"))
      (node (ref "R20") (pin "2") (pinfunction "2_2") (pintype "passive"))
    )
    (net (code "56") (name "Net-(U1-PROG)") (class "Default")
      (node (ref "R12") (pin "2") (pinfunction "2_2") (pintype "passive"))
      (node (ref "R13") (pin "2") (pinfunction "2_2") (pintype "passive"))
      (node (ref "U1") (pin "2") (pinfunction "PROG_2") (pintype "passive"))
    )
    (net (code "57") (name "Net-(U2-NRST)") (class "Default")
      (node (ref "C9") (pin "2") (pinfunction "2_2") (pintype "passive"))
      (node (ref "U2") (pin "7") (pinfunction "NRST_7") (pintype "bidirectional"))
    )
    (net (code "58") (name "Net-(U2-PD0_OSC_IN)") (class "Default")
      (node (ref "C7") (pin "2") (pinfunction "2_2") (pintype "passive"))
      (node (ref "U2") (pin "5") (pinfunction "PD0_OSC_IN_5") (pintype "passive"))
      (node (ref "X1") (pin "1") (pinfunction "X1_1") (pintype "passive"))
    )
    (net (code "59") (name "Net-(U2-PD1_OSC_OUT)") (class "Default")
      (node (ref "C8") (pin "2") (pinfunction "2_2") (pintype "passive"))
      (node (ref "U2") (pin "6") (pinfunction "PD1_OSC_OUT_6") (pintype "passive"))
      (node (ref "X1") (pin "3") (pinfunction "X2_3") (pintype "passive"))
    )
    (net (code "60") (name "Net-(U2-Vcap1)") (class "Default")
      (node (ref "C11") (pin "2") (pinfunction "2_2") (pintype "passive"))
      (node (ref "U2") (pin "31") (pinfunction "Vcap1_31") (pintype "power_in"))
    )
    (net (code "61") (name "Net-(U2-Vcap2)") (class "Default")
      (node (ref "C10") (pin "2") (pinfunction "2_2") (pintype "passive"))
      (node (ref "U2") (pin "47") (pinfunction "Vcap2_47") (pintype "power_in"))
    )
    (net (code "62") (name "VB") (class "Default")
      (node (ref "J1") (pin "1") (pinfunction "1_1") (pintype "passive"))
      (node (ref "J4") (pin "1") (pinfunction "1_1") (pintype "passive"))
    )
    (net (code "63") (name "VBAT") (class "Default")
      (node (ref "C1") (pin "2") (pinfunction "2_2") (pintype "passive"))
      (node (ref "J1") (pin "2") (pinfunction "2_2") (pintype "passive"))
      (node (ref "Q1") (pin "2") (pinfunction "SOURCE_2") (pintype "passive"))
      (node (ref "R18") (pin "2") (pinfunction "2_2") (pintype "passive"))
      (node (ref "U1") (pin "5") (pinfunction "BAT_5") (pintype "passive"))
    )
    (net (code "64") (name "VSYS") (class "Default")
      (node (ref "C5") (pin "2") (pinfunction "2_2") (pintype "passive"))
      (node (ref "Q1") (pin "3") (pinfunction "DRAIN_3") (pintype "passive"))
      (node (ref "R11") (pin "2") (pinfunction "2_2") (pintype "passive"))
      (node (ref "U3") (pin "3") (pinfunction "VIN_3") (pintype "passive"))
    )
    (net (code "65") (name "unconnected-(J1-Pad3)") (class "Default")
      (node (ref "J1") (pin "3") (pinfunction "3_3") (pintype "passive"))
    )
    (net (code "66") (name "unconnected-(J2-ID-Pad4)") (class "Default")
      (node (ref "J2") (pin "4") (pinfunction "ID_4") (pintype "passive"))
    )
    (net (code "67") (name "unconnected-(SW1-Pad1)") (class "Default")
      (node (ref "SW1") (pin "1") (pinfunction "1_1") (pintype "passive"))
    )
    (net (code "68") (name "unconnected-(SW1-Pad4)") (class "Default")
      (node (ref "SW1") (pin "4") (pinfunction "4_4") (pintype "passive"))
    )
    (net (code "69") (name "unconnected-(SW4-Pad4)") (class "Default")
      (node (ref "SW4") (pin "4") (pinfunction "4_4") (pintype "passive"))
    )
    (net (code "70") (name "unconnected-(U2-PB6-Pad58)") (class "Default")
      (node (ref "U2") (pin "58") (pinfunction "PB6_58") (pintype "bidirectional"))
    )
    (net (code "71") (name "unconnected-(U2-PB7-Pad59)") (class "Default")
      (node (ref "U2") (pin "59") (pinfunction "PB7_59") (pintype "bidirectional"))
    )
    (net (code "72") (name "unconnected-(U2-PB8-Pad61)") (class "Default")
      (node (ref "U2") (pin "61") (pinfunction "PB8_61") (pintype "bidirectional"))
    )
    (net (code "73") (name "unconnected-(U2-PB9-Pad62)") (class "Default")
      (node (ref "U2") (pin "62") (pinfunction "PB9_62") (pintype "bidirectional"))
    )
    (net (code "74") (name "unconnected-(U2-PB13-Pad34)") (class "Default")
      (node (ref "U2") (pin "34") (pinfunction "PB13_34") (pintype "bidirectional"))
    )
    (net (code "75") (name "unconnected-(U2-PB14-Pad35)") (class "Default")
      (node (ref "U2") (pin "35") (pinfunction "PB14_35") (pintype "bidirectional"))
    )
    (net (code "76") (name "unconnected-(U2-PC0-Pad8)") (class "Default")
      (node (ref "U2") (pin "8") (pinfunction "PC0_8") (pintype "bidirectional"))
    )
    (net (code "77") (name "unconnected-(U2-PC1-Pad9)") (class "Default")
      (node (ref "U2") (pin "9") (pinfunction "PC1_9") (pintype "bidirectional"))
    )
    (net (code "78") (name "unconnected-(U2-PC2-Pad10)") (class "Default")
      (node (ref "U2") (pin "10") (pinfunction "PC2_10") (pintype "bidirectional"))
    )
    (net (code "79") (name "unconnected-(U2-PC3-Pad11)") (class "Default")
      (node (ref "U2") (pin "11") (pinfunction "PC3_11") (pintype "bidirectional"))
    )
    (net (code "80") (name "unconnected-(U2-PC6-Pad37)") (class "Default")
      (node (ref "U2") (pin "37") (pinfunction "PC6_37") (pintype "bidirectional"))
    )
    (net (code "81") (name "unconnected-(U2-PC9-Pad40)") (class "Default")
      (node (ref "U2") (pin "40") (pinfunction "PC9_40") (pintype "bidirectional"))
    )
    (net (code "82") (name "unconnected-(U2-PC12-Pad53)") (class "Default")
      (node (ref "U2") (pin "53") (pinfunction "PC12_53") (pintype "bidirectional"))
    )
    (net (code "83") (name "unconnected-(U2-PC13-TAMPER-RTC-Pad2)") (class "Default")
      (node (ref "U2") (pin "2") (pinfunction "PC13-TAMPER-RTC_2") (pintype "bidirectional"))
    )
  )
)
